# EstmetSquematic.net
KiCad netlist of a schematic drawn in Altium Designer
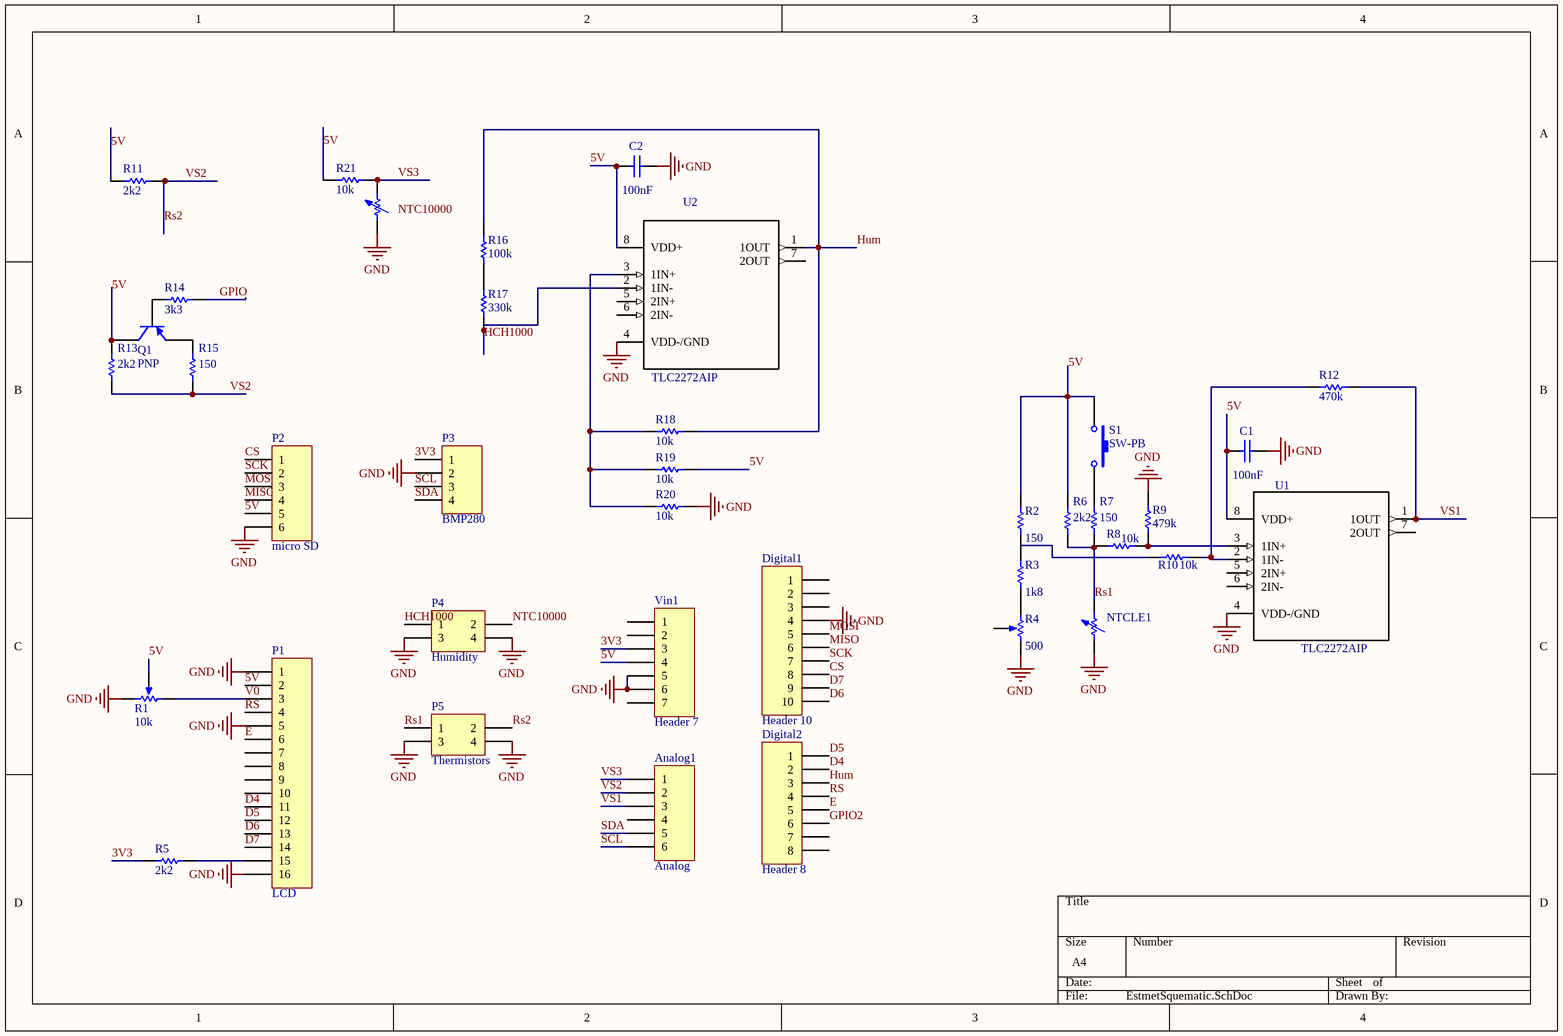
[diagram p0: EstmetSquematic.SchDoc]

(export (version "E")
  (design (tool "Eeschema 10.0.6"))
  (components
    (comp (ref "Analog1")
      (value "Analog")
      (footprint "HDR1X6")
      (description "Header, 6-Pin")
      (fields (field (name "PUBLISHER") "Altium Limited"))
      (libsource (lib "Miscellaneous Connectors") (part "Header 6"))
    )
    (comp (ref "C1")
      (value "100nF")
      (footprint "RAD-0.3")
      (description "Capacitor")
      (fields (field (name "Comment") "Cap") (field (name "PUBLISHER") "Altium Limited"))
      (libsource (lib "Miscellaneous Devices") (part "Cap"))
    )
    (comp (ref "C2")
      (value "100nF")
      (footprint "RAD-0.3")
      (description "Capacitor")
      (fields (field (name "Comment") "Cap") (field (name "PUBLISHER") "Altium Limited"))
      (libsource (lib "Miscellaneous Devices") (part "Cap"))
    )
    (comp (ref "Digital1")
      (value "Header 10")
      (footprint "HDR1X10")
      (description "Header, 10-Pin")
      (fields (field (name "PUBLISHER") "Altium Limited"))
      (libsource (lib "Miscellaneous Connectors") (part "Header 10"))
    )
    (comp (ref "Digital2")
      (value "Header 8")
      (footprint "HDR1X8")
      (description "Header, 8-Pin")
      (fields (field (name "PUBLISHER") "Altium Limited"))
      (libsource (lib "Miscellaneous Connectors") (part "Header 8"))
    )
    (comp (ref "NTCLE")
      (value "Res Adj1")
      (footprint "AXIAL-0.7")
      (description "Variable Resistor")
      (fields (field (name "PUBLISHER") "Altium Limited"))
      (libsource (lib "Miscellaneous Devices") (part "Res Adj1"))
    )
    (comp (ref "NTCLE1")
      (value "Res Adj1")
      (footprint "AXIAL-0.7")
      (description "Variable Resistor")
      (fields (field (name "PUBLISHER") "Altium Limited"))
      (libsource (lib "Miscellaneous Devices") (part "Res Adj1"))
    )
    (comp (ref "P1")
      (value "LCD")
      (footprint "HDR1X16")
      (description "Header, 16-Pin")
      (fields (field (name "PUBLISHER") "Altium Limited"))
      (libsource (lib "Miscellaneous Connectors") (part "Header 16"))
    )
    (comp (ref "P2")
      (value "micro SD")
      (footprint "HDR1X6")
      (description "Header, 6-Pin")
      (fields (field (name "PUBLISHER") "Altium Limited"))
      (libsource (lib "Miscellaneous Connectors") (part "Header 6"))
    )
    (comp (ref "P3")
      (value "BMP280")
      (footprint "HDR1X4")
      (description "Header, 4-Pin")
      (fields (field (name "PUBLISHER") "Altium Limited"))
      (libsource (lib "Miscellaneous Connectors") (part "Header 4"))
    )
    (comp (ref "P4")
      (value "Humidity")
      (footprint "HDR2X2")
      (description "Header, 2-Pin, Dual row")
      (fields (field (name "PUBLISHER") "Altium Limited"))
      (libsource (lib "Miscellaneous Connectors") (part "Header 2X2"))
    )
    (comp (ref "P5")
      (value "Thermistors")
      (footprint "HDR2X2")
      (description "Header, 2-Pin, Dual row")
      (fields (field (name "PUBLISHER") "Altium Limited"))
      (libsource (lib "Miscellaneous Connectors") (part "Header 2X2"))
    )
    (comp (ref "Q1")
      (value "PNP")
      (footprint "SOT-23B_N")
      (description "PNP Bipolar Transistor")
      (fields (field (name "PUBLISHER") "Altium Limited"))
      (libsource (lib "Miscellaneous Devices") (part "PNP"))
    )
    (comp (ref "R1")
      (value "10k")
      (footprint "VR5")
      (description "Potentiometer")
      (fields (field (name "Comment") "RPot") (field (name "PUBLISHER") "Altium Limited"))
      (libsource (lib "Miscellaneous Devices") (part "RPot"))
    )
    (comp (ref "R2")
      (value "150")
      (footprint "AXIAL-0.3")
      (description "Resistor")
      (fields (field (name "Comment") "Res1") (field (name "PUBLISHER") "Altium Limited"))
      (libsource (lib "Miscellaneous Devices") (part "Res1"))
    )
    (comp (ref "R3")
      (value "1k8")
      (footprint "AXIAL-0.3")
      (description "Resistor")
      (fields (field (name "Comment") "Res1") (field (name "PUBLISHER") "Altium Limited"))
      (libsource (lib "Miscellaneous Devices") (part "Res1"))
    )
    (comp (ref "R4")
      (value "500")
      (footprint "VR5")
      (description "Potentiometer")
      (fields (field (name "Comment") "RPot") (field (name "PUBLISHER") "Altium Limited"))
      (libsource (lib "Miscellaneous Devices") (part "RPot"))
    )
    (comp (ref "R5")
      (value "2k2")
      (footprint "AXIAL-0.3")
      (description "Resistor")
      (fields (field (name "Comment") "Res1") (field (name "PUBLISHER") "Altium Limited"))
      (libsource (lib "Miscellaneous Devices") (part "Res1"))
    )
    (comp (ref "R6")
      (value "2k2")
      (footprint "AXIAL-0.3")
      (description "Resistor")
      (fields (field (name "Comment") "Res1") (field (name "PUBLISHER") "Altium Limited"))
      (libsource (lib "Miscellaneous Devices") (part "Res1"))
    )
    (comp (ref "R7")
      (value "150")
      (footprint "AXIAL-0.3")
      (description "Resistor")
      (fields (field (name "Comment") "Res1") (field (name "PUBLISHER") "Altium Limited"))
      (libsource (lib "Miscellaneous Devices") (part "Res1"))
    )
    (comp (ref "R8")
      (value "10k")
      (footprint "AXIAL-0.3")
      (description "Resistor")
      (fields (field (name "Comment") "Res1") (field (name "PUBLISHER") "Altium Limited"))
      (libsource (lib "Miscellaneous Devices") (part "Res1"))
    )
    (comp (ref "R9")
      (value "479k")
      (footprint "AXIAL-0.3")
      (description "Resistor")
      (fields (field (name "Comment") "Res1") (field (name "PUBLISHER") "Altium Limited"))
      (libsource (lib "Miscellaneous Devices") (part "Res1"))
    )
    (comp (ref "R10")
      (value "10k")
      (footprint "AXIAL-0.3")
      (description "Resistor")
      (fields (field (name "Comment") "Res1") (field (name "PUBLISHER") "Altium Limited"))
      (libsource (lib "Miscellaneous Devices") (part "Res1"))
    )
    (comp (ref "R11")
      (value "2k2")
      (footprint "AXIAL-0.3")
      (description "Resistor")
      (fields (field (name "Comment") "Res1") (field (name "PUBLISHER") "Altium Limited"))
      (libsource (lib "Miscellaneous Devices") (part "Res1"))
    )
    (comp (ref "R12")
      (value "470k")
      (footprint "AXIAL-0.3")
      (description "Resistor")
      (fields (field (name "Comment") "Res1") (field (name "PUBLISHER") "Altium Limited"))
      (libsource (lib "Miscellaneous Devices") (part "Res1"))
    )
    (comp (ref "R13")
      (value "2k2")
      (footprint "AXIAL-0.3")
      (description "Resistor")
      (fields (field (name "Comment") "Res1") (field (name "PUBLISHER") "Altium Limited"))
      (libsource (lib "Miscellaneous Devices") (part "Res1"))
    )
    (comp (ref "R14")
      (value "3k3")
      (footprint "AXIAL-0.3")
      (description "Resistor")
      (fields (field (name "Comment") "Res1") (field (name "PUBLISHER") "Altium Limited"))
      (libsource (lib "Miscellaneous Devices") (part "Res1"))
    )
    (comp (ref "R15")
      (value "150")
      (footprint "AXIAL-0.3")
      (description "Resistor")
      (fields (field (name "Comment") "Res1") (field (name "PUBLISHER") "Altium Limited"))
      (libsource (lib "Miscellaneous Devices") (part "Res1"))
    )
    (comp (ref "R16")
      (value "100k")
      (footprint "AXIAL-0.3")
      (description "Resistor")
      (fields (field (name "Comment") "Res1") (field (name "PUBLISHER") "Altium Limited"))
      (libsource (lib "Miscellaneous Devices") (part "Res1"))
    )
    (comp (ref "R17")
      (value "330k")
      (footprint "AXIAL-0.3")
      (description "Resistor")
      (fields (field (name "Comment") "Res1") (field (name "PUBLISHER") "Altium Limited"))
      (libsource (lib "Miscellaneous Devices") (part "Res1"))
    )
    (comp (ref "R18")
      (value "10k")
      (footprint "AXIAL-0.3")
      (description "Resistor")
      (fields (field (name "Comment") "Res1") (field (name "PUBLISHER") "Altium Limited"))
      (libsource (lib "Miscellaneous Devices") (part "Res1"))
    )
    (comp (ref "R19")
      (value "10k")
      (footprint "AXIAL-0.3")
      (description "Resistor")
      (fields (field (name "Comment") "Res1") (field (name "PUBLISHER") "Altium Limited"))
      (libsource (lib "Miscellaneous Devices") (part "Res1"))
    )
    (comp (ref "R20")
      (value "10k")
      (footprint "AXIAL-0.3")
      (description "Resistor")
      (fields (field (name "Comment") "Res1") (field (name "PUBLISHER") "Altium Limited"))
      (libsource (lib "Miscellaneous Devices") (part "Res1"))
    )
    (comp (ref "R21")
      (value "10k")
      (footprint "AXIAL-0.3")
      (description "Resistor")
      (fields (field (name "Comment") "Res1") (field (name "PUBLISHER") "Altium Limited"))
      (libsource (lib "Miscellaneous Devices") (part "Res1"))
    )
    (comp (ref "S1")
      (value "SW-PB")
      (footprint "SPST-2")
      (description "Switch")
      (fields (field (name "PUBLISHER") "Altium Limited"))
      (libsource (lib "Miscellaneous Devices") (part "SW-PB"))
    )
    (comp (ref "U1")
      (value "TLC2272AIP")
      (footprint "*DIP254P762X508-8")
      (description "Advanced LinCMOS_TM_ ail-To- ail Dual Operational Amplifier 8-PDIP")
      (fields (field (name "MF") "Texas Instruments"))
      (libsource (lib "TLC2272AIP") (part "TLC2272AIP"))
    )
    (comp (ref "U2")
      (value "TLC2272AIP")
      (footprint "*DIP254P762X508-8")
      (description "Advanced LinCMOS_TM_ ail-To- ail Dual Operational Amplifier 8-PDIP")
      (fields (field (name "MF") "Texas Instruments"))
      (libsource (lib "TLC2272AIP") (part "TLC2272AIP"))
    )
    (comp (ref "Vin1")
      (value "Header 7")
      (footprint "HDR1X7")
      (description "Header, 7-Pin")
      (fields (field (name "PUBLISHER") "Altium Limited"))
      (libsource (lib "Miscellaneous Connectors") (part "Header 7"))
    )
  )
  (nets
    (net (code "1") (name "/3V3") (class "Default")
      (node (ref "P3") (pin "1") (pinfunction "1_1") (pintype "passive"))
      (node (ref "R5") (pin "2") (pinfunction "2_2") (pintype "passive"))
      (node (ref "Vin1") (pin "3") (pinfunction "3_3") (pintype "passive"))
    )
    (net (code "2") (name "/5V") (class "Default")
      (node (ref "C1") (pin "1") (pinfunction "1_1") (pintype "passive"))
      (node (ref "C2") (pin "1") (pinfunction "1_1") (pintype "passive"))
      (node (ref "P1") (pin "2") (pinfunction "2_2") (pintype "passive"))
      (node (ref "P2") (pin "5") (pinfunction "5_5") (pintype "passive"))
      (node (ref "Q1") (pin "1") (pinfunction "C_1") (pintype "passive"))
      (node (ref "R1") (pin "3") (pinfunction "TAP_3") (pintype "passive"))
      (node (ref "R11") (pin "2") (pinfunction "2_2") (pintype "passive"))
      (node (ref "R13") (pin "2") (pinfunction "2_2") (pintype "passive"))
      (node (ref "R19") (pin "1") (pinfunction "1_1") (pintype "passive"))
      (node (ref "R21") (pin "2") (pinfunction "2_2") (pintype "passive"))
      (node (ref "U1") (pin "8") (pinfunction "VDD+_8") (pintype "power_in"))
      (node (ref "U2") (pin "8") (pinfunction "VDD+_8") (pintype "power_in"))
      (node (ref "Vin1") (pin "4") (pinfunction "4_4") (pintype "passive"))
    )
    (net (code "3") (name "/CS") (class "Default")
      (node (ref "Digital1") (pin "8") (pinfunction "8_8") (pintype "passive"))
      (node (ref "P2") (pin "1") (pinfunction "1_1") (pintype "passive"))
    )
    (net (code "4") (name "/D4") (class "Default")
      (node (ref "Digital2") (pin "2") (pinfunction "2_2") (pintype "passive"))
      (node (ref "P1") (pin "11") (pinfunction "11_11") (pintype "passive"))
    )
    (net (code "5") (name "/D5") (class "Default")
      (node (ref "Digital2") (pin "1") (pinfunction "1_1") (pintype "passive"))
      (node (ref "P1") (pin "12") (pinfunction "12_12") (pintype "passive"))
    )
    (net (code "6") (name "/D6") (class "Default")
      (node (ref "Digital1") (pin "10") (pinfunction "10_10") (pintype "passive"))
      (node (ref "P1") (pin "13") (pinfunction "13_13") (pintype "passive"))
    )
    (net (code "7") (name "/D7") (class "Default")
      (node (ref "Digital1") (pin "9") (pinfunction "9_9") (pintype "passive"))
      (node (ref "P1") (pin "14") (pinfunction "14_14") (pintype "passive"))
    )
    (net (code "8") (name "/E") (class "Default")
      (node (ref "Digital2") (pin "5") (pinfunction "5_5") (pintype "passive"))
      (node (ref "P1") (pin "6") (pinfunction "6_6") (pintype "passive"))
    )
    (net (code "9") (name "/GPIO") (class "Default")
      (node (ref "R14") (pin "1") (pinfunction "1_1") (pintype "passive"))
    )
    (net (code "10") (name "/GPIO2") (class "Default")
      (node (ref "Digital2") (pin "6") (pinfunction "6_6") (pintype "passive"))
    )
    (net (code "11") (name "/HCH1000") (class "Default")
      (node (ref "P4") (pin "1") (pinfunction "1_1") (pintype "passive"))
      (node (ref "R17") (pin "2") (pinfunction "2_2") (pintype "passive"))
      (node (ref "U2") (pin "2") (pinfunction "1IN-_2") (pintype "input"))
    )
    (net (code "12") (name "/Hum") (class "Default")
      (node (ref "Digital2") (pin "3") (pinfunction "3_3") (pintype "passive"))
      (node (ref "R16") (pin "1") (pinfunction "1_1") (pintype "passive"))
      (node (ref "R18") (pin "1") (pinfunction "1_1") (pintype "passive"))
      (node (ref "U2") (pin "1") (pinfunction "1OUT_1") (pintype "output"))
    )
    (net (code "13") (name "/MISO") (class "Default")
      (node (ref "Digital1") (pin "6") (pinfunction "6_6") (pintype "passive"))
      (node (ref "P2") (pin "4") (pinfunction "4_4") (pintype "passive"))
    )
    (net (code "14") (name "/MOSI") (class "Default")
      (node (ref "Digital1") (pin "5") (pinfunction "5_5") (pintype "passive"))
      (node (ref "P2") (pin "3") (pinfunction "3_3") (pintype "passive"))
    )
    (net (code "15") (name "/NTC10000") (class "Default")
      (node (ref "P4") (pin "2") (pinfunction "2_2") (pintype "passive"))
    )
    (net (code "16") (name "/RS") (class "Default")
      (node (ref "Digital2") (pin "4") (pinfunction "4_4") (pintype "passive"))
      (node (ref "P1") (pin "4") (pinfunction "4_4") (pintype "passive"))
    )
    (net (code "17") (name "/Rs1") (class "Default")
      (node (ref "NTCLE1") (pin "2") (pinfunction "2_2") (pintype "passive"))
      (node (ref "P5") (pin "1") (pinfunction "1_1") (pintype "passive"))
      (node (ref "R6") (pin "1") (pinfunction "1_1") (pintype "passive"))
      (node (ref "R7") (pin "1") (pinfunction "1_1") (pintype "passive"))
      (node (ref "R8") (pin "2") (pinfunction "2_2") (pintype "passive"))
    )
    (net (code "18") (name "/Rs2") (class "Default")
      (node (ref "Analog1") (pin "2") (pinfunction "2_2") (pintype "passive"))
      (node (ref "P5") (pin "2") (pinfunction "2_2") (pintype "passive"))
      (node (ref "R11") (pin "1") (pinfunction "1_1") (pintype "passive"))
      (node (ref "R13") (pin "1") (pinfunction "1_1") (pintype "passive"))
      (node (ref "R15") (pin "1") (pinfunction "1_1") (pintype "passive"))
    )
    (net (code "19") (name "/SCK") (class "Default")
      (node (ref "Digital1") (pin "7") (pinfunction "7_7") (pintype "passive"))
      (node (ref "P2") (pin "2") (pinfunction "2_2") (pintype "passive"))
    )
    (net (code "20") (name "/SCL") (class "Default")
      (node (ref "Analog1") (pin "6") (pinfunction "6_6") (pintype "passive"))
      (node (ref "P3") (pin "3") (pinfunction "3_3") (pintype "passive"))
    )
    (net (code "21") (name "/SDA") (class "Default")
      (node (ref "Analog1") (pin "5") (pinfunction "5_5") (pintype "passive"))
      (node (ref "P3") (pin "4") (pinfunction "4_4") (pintype "passive"))
    )
    (net (code "22") (name "/V0") (class "Default")
      (node (ref "P1") (pin "3") (pinfunction "3_3") (pintype "passive"))
      (node (ref "R1") (pin "1") (pinfunction "TOP_1") (pintype "passive"))
    )
    (net (code "23") (name "/VS1") (class "Default")
      (node (ref "Analog1") (pin "3") (pinfunction "3_3") (pintype "passive"))
      (node (ref "R12") (pin "1") (pinfunction "1_1") (pintype "passive"))
      (node (ref "U1") (pin "1") (pinfunction "1OUT_1") (pintype "output"))
    )
    (net (code "24") (name "/VS3") (class "Default")
      (node (ref "Analog1") (pin "1") (pinfunction "1_1") (pintype "passive"))
      (node (ref "NTCLE") (pin "2") (pinfunction "2_2") (pintype "passive"))
      (node (ref "R21") (pin "1") (pinfunction "1_1") (pintype "passive"))
    )
    (net (code "25") (name "GND") (class "Default")
      (node (ref "C1") (pin "2") (pinfunction "2_2") (pintype "passive"))
      (node (ref "C2") (pin "2") (pinfunction "2_2") (pintype "passive"))
      (node (ref "Digital1") (pin "4") (pinfunction "4_4") (pintype "passive"))
      (node (ref "NTCLE") (pin "1") (pinfunction "1_1") (pintype "passive"))
      (node (ref "NTCLE1") (pin "1") (pinfunction "1_1") (pintype "passive"))
      (node (ref "P1") (pin "1") (pinfunction "1_1") (pintype "passive"))
      (node (ref "P1") (pin "16") (pinfunction "16_16") (pintype "passive"))
      (node (ref "P1") (pin "5") (pinfunction "5_5") (pintype "passive"))
      (node (ref "P2") (pin "6") (pinfunction "6_6") (pintype "passive"))
      (node (ref "P3") (pin "2") (pinfunction "2_2") (pintype "passive"))
      (node (ref "P4") (pin "3") (pinfunction "3_3") (pintype "passive"))
      (node (ref "P4") (pin "4") (pinfunction "4_4") (pintype "passive"))
      (node (ref "P5") (pin "3") (pinfunction "3_3") (pintype "passive"))
      (node (ref "P5") (pin "4") (pinfunction "4_4") (pintype "passive"))
      (node (ref "R1") (pin "2") (pinfunction "BOT_2") (pintype "passive"))
      (node (ref "R20") (pin "1") (pinfunction "1_1") (pintype "passive"))
      (node (ref "R4") (pin "2") (pinfunction "BOT_2") (pintype "passive"))
      (node (ref "R9") (pin "1") (pinfunction "1_1") (pintype "passive"))
      (node (ref "U1") (pin "4") (pinfunction "VDD-/GND_4") (pintype "passive"))
      (node (ref "U2") (pin "4") (pinfunction "VDD-/GND_4") (pintype "passive"))
      (node (ref "Vin1") (pin "5") (pinfunction "5_5") (pintype "passive"))
      (node (ref "Vin1") (pin "6") (pinfunction "6_6") (pintype "passive"))
    )
    (net (code "26") (name "Net-(P1-Pad15)") (class "Default")
      (node (ref "P1") (pin "15") (pinfunction "15_15") (pintype "passive"))
      (node (ref "R5") (pin "1") (pinfunction "1_1") (pintype "passive"))
    )
    (net (code "27") (name "Net-(Q1-B)") (class "Default")
      (node (ref "Q1") (pin "2") (pinfunction "B_2") (pintype "passive"))
      (node (ref "R14") (pin "2") (pinfunction "2_2") (pintype "passive"))
    )
    (net (code "28") (name "Net-(Q1-E)") (class "Default")
      (node (ref "Q1") (pin "3") (pinfunction "E_3") (pintype "passive"))
      (node (ref "R15") (pin "2") (pinfunction "2_2") (pintype "passive"))
    )
    (net (code "29") (name "Net-(R2-Pad1)") (class "Default")
      (node (ref "R2") (pin "1") (pinfunction "1_1") (pintype "passive"))
      (node (ref "R3") (pin "2") (pinfunction "2_2") (pintype "passive"))
    )
    (net (code "30") (name "Net-(R2-Pad2)") (class "Default")
      (node (ref "R2") (pin "2") (pinfunction "2_2") (pintype "passive"))
      (node (ref "R6") (pin "2") (pinfunction "2_2") (pintype "passive"))
      (node (ref "S1") (pin "1") (pinfunction "1_1") (pintype "passive"))
    )
    (net (code "31") (name "Net-(R4-TOP)") (class "Default")
      (node (ref "R3") (pin "1") (pinfunction "1_1") (pintype "passive"))
      (node (ref "R4") (pin "1") (pinfunction "TOP_1") (pintype "passive"))
    )
    (net (code "32") (name "Net-(R7-Pad2)") (class "Default")
      (node (ref "R7") (pin "2") (pinfunction "2_2") (pintype "passive"))
      (node (ref "S1") (pin "2") (pinfunction "2_2") (pintype "passive"))
    )
    (net (code "33") (name "Net-(R16-Pad2)") (class "Default")
      (node (ref "R16") (pin "2") (pinfunction "2_2") (pintype "passive"))
      (node (ref "R17") (pin "1") (pinfunction "1_1") (pintype "passive"))
    )
    (net (code "34") (name "Net-(U1-1IN+)") (class "Default")
      (node (ref "R8") (pin "1") (pinfunction "1_1") (pintype "passive"))
      (node (ref "R9") (pin "2") (pinfunction "2_2") (pintype "passive"))
      (node (ref "U1") (pin "3") (pinfunction "1IN+_3") (pintype "input"))
    )
    (net (code "35") (name "Net-(U1-1IN-)") (class "Default")
      (node (ref "R10") (pin "1") (pinfunction "1_1") (pintype "passive"))
      (node (ref "R12") (pin "2") (pinfunction "2_2") (pintype "passive"))
      (node (ref "U1") (pin "2") (pinfunction "1IN-_2") (pintype "input"))
    )
    (net (code "36") (name "Net-(U2-1IN+)") (class "Default")
      (node (ref "R18") (pin "2") (pinfunction "2_2") (pintype "passive"))
      (node (ref "R19") (pin "2") (pinfunction "2_2") (pintype "passive"))
      (node (ref "R20") (pin "2") (pinfunction "2_2") (pintype "passive"))
      (node (ref "U2") (pin "3") (pinfunction "1IN+_3") (pintype "input"))
    )
    (net (code "37") (name "unconnected-(Analog1-Pad4)") (class "Default")
      (node (ref "Analog1") (pin "4") (pinfunction "4_4") (pintype "passive"))
    )
    (net (code "38") (name "unconnected-(Digital1-Pad1)") (class "Default")
      (node (ref "Digital1") (pin "1") (pinfunction "1_1") (pintype "passive"))
    )
    (net (code "39") (name "unconnected-(Digital1-Pad2)") (class "Default")
      (node (ref "Digital1") (pin "2") (pinfunction "2_2") (pintype "passive"))
    )
    (net (code "40") (name "unconnected-(Digital1-Pad3)") (class "Default")
      (node (ref "Digital1") (pin "3") (pinfunction "3_3") (pintype "passive"))
    )
    (net (code "41") (name "unconnected-(Digital2-Pad7)") (class "Default")
      (node (ref "Digital2") (pin "7") (pinfunction "7_7") (pintype "passive"))
    )
    (net (code "42") (name "unconnected-(Digital2-Pad8)") (class "Default")
      (node (ref "Digital2") (pin "8") (pinfunction "8_8") (pintype "passive"))
    )
    (net (code "43") (name "unconnected-(P1-Pad7)") (class "Default")
      (node (ref "P1") (pin "7") (pinfunction "7_7") (pintype "passive"))
    )
    (net (code "44") (name "unconnected-(P1-Pad8)") (class "Default")
      (node (ref "P1") (pin "8") (pinfunction "8_8") (pintype "passive"))
    )
    (net (code "45") (name "unconnected-(P1-Pad9)") (class "Default")
      (node (ref "P1") (pin "9") (pinfunction "9_9") (pintype "passive"))
    )
    (net (code "46") (name "unconnected-(P1-Pad10)") (class "Default")
      (node (ref "P1") (pin "10") (pinfunction "10_10") (pintype "passive"))
    )
    (net (code "47") (name "unconnected-(R4-TAP-Pad3)") (class "Default")
      (node (ref "R4") (pin "3") (pinfunction "TAP_3") (pintype "passive"))
    )
    (net (code "48") (name "unconnected-(R10-Pad2)") (class "Default")
      (node (ref "R10") (pin "2") (pinfunction "2_2") (pintype "passive"))
    )
    (net (code "49") (name "unconnected-(U1-2IN+-Pad5)") (class "Default")
      (node (ref "U1") (pin "5") (pinfunction "2IN+_5") (pintype "input"))
    )
    (net (code "50") (name "unconnected-(U1-2IN--Pad6)") (class "Default")
      (node (ref "U1") (pin "6") (pinfunction "2IN-_6") (pintype "input"))
    )
    (net (code "51") (name "unconnected-(U1-2OUT-Pad7)") (class "Default")
      (node (ref "U1") (pin "7") (pinfunction "2OUT_7") (pintype "output"))
    )
    (net (code "52") (name "unconnected-(U2-2IN+-Pad5)") (class "Default")
      (node (ref "U2") (pin "5") (pinfunction "2IN+_5") (pintype "input"))
    )
    (net (code "53") (name "unconnected-(U2-2IN--Pad6)") (class "Default")
      (node (ref "U2") (pin "6") (pinfunction "2IN-_6") (pintype "input"))
    )
    (net (code "54") (name "unconnected-(U2-2OUT-Pad7)") (class "Default")
      (node (ref "U2") (pin "7") (pinfunction "2OUT_7") (pintype "output"))
    )
    (net (code "55") (name "unconnected-(Vin1-Pad1)") (class "Default")
      (node (ref "Vin1") (pin "1") (pinfunction "1_1") (pintype "passive"))
    )
    (net (code "56") (name "unconnected-(Vin1-Pad2)") (class "Default")
      (node (ref "Vin1") (pin "2") (pinfunction "2_2") (pintype "passive"))
    )
    (net (code "57") (name "unconnected-(Vin1-Pad7)") (class "Default")
      (node (ref "Vin1") (pin "7") (pinfunction "7_7") (pintype "passive"))
    )
  )
)
